# schematics.net
KiCad netlist of a schematic drawn in EAGLE
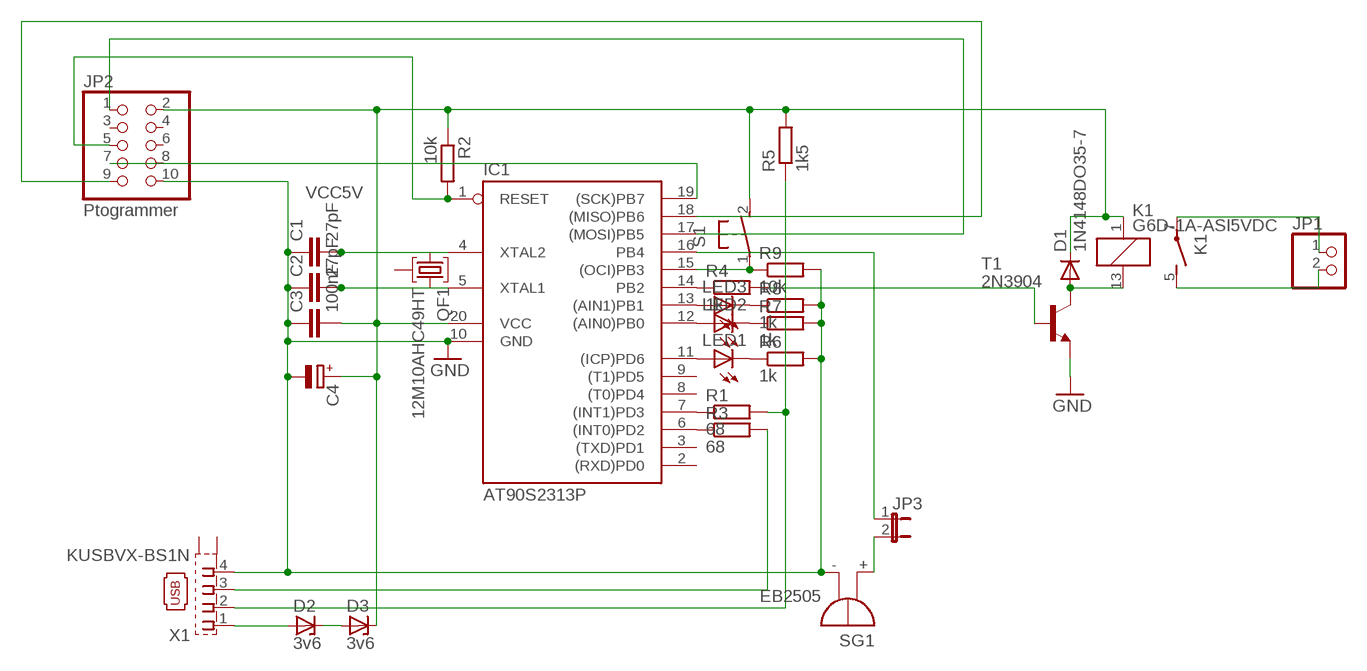
[diagram p0: schematic, sheet 1]

(export (version "E")
  (design (tool "Eeschema 10.0.6"))
  (components
    (comp (ref "C1")
      (value "27pF")
      (footprint "eagle-import:C025-024X044")
      (libsource (lib "eagle-import") (part "C-EU025-024X044"))
    )
    (comp (ref "C2")
      (value "27pF")
      (footprint "eagle-import:C025-024X044")
      (libsource (lib "eagle-import") (part "C-EU025-024X044"))
    )
    (comp (ref "C3")
      (value "100nF")
      (footprint "eagle-import:C025-024X044")
      (libsource (lib "eagle-import") (part "C-EU025-024X044"))
    )
    (comp (ref "C4")
      (value "CPOL-EUE2.5-7")
      (footprint "eagle-import:E2,5-7")
      (libsource (lib "eagle-import") (part "CPOL-EUE2.5-7"))
    )
    (comp (ref "D1")
      (value "1N4148DO35-7")
      (footprint "eagle-import:DO35-7")
      (libsource (lib "eagle-import") (part "1N4148DO35-7"))
    )
    (comp (ref "D2")
      (value "3v6")
      (footprint "eagle-import:DO35Z10")
      (libsource (lib "eagle-import") (part "ZENER-DIODEDO35Z10"))
    )
    (comp (ref "D3")
      (value "3v6")
      (footprint "eagle-import:DO35Z10")
      (libsource (lib "eagle-import") (part "ZENER-DIODEDO35Z10"))
    )
    (comp (ref "IC1")
      (value "AT90S2313P")
      (footprint "eagle-import:DIL20")
      (libsource (lib "eagle-import") (part "AT90S2313P"))
    )
    (comp (ref "JP1")
      (value "PINHD-1X2/90")
      (footprint "eagle-import:1X02_90")
      (libsource (lib "eagle-import") (part "PINHD-1X2/90"))
    )
    (comp (ref "JP2")
      (value "Ptogrammer")
      (footprint "eagle-import:2X05")
      (libsource (lib "eagle-import") (part "PINHD-2X5"))
    )
    (comp (ref "JP3")
      (value "JP1E")
      (footprint "eagle-import:JP1")
      (libsource (lib "eagle-import") (part "JP1E"))
    )
    (comp (ref "K1")
      (value "G6D-1A-ASI5VDC")
      (footprint "eagle-import:G6D")
      (libsource (lib "eagle-import") (part "G6D?-1A-ASI5VDC"))
    )
    (comp (ref "LED1")
      (value "LED3MM")
      (footprint "eagle-import:LED3MM")
      (libsource (lib "eagle-import") (part "LED3MM"))
    )
    (comp (ref "LED2")
      (value "LED3MM")
      (footprint "eagle-import:LED3MM")
      (libsource (lib "eagle-import") (part "LED3MM"))
    )
    (comp (ref "LED3")
      (value "LED3MM")
      (footprint "eagle-import:LED3MM")
      (libsource (lib "eagle-import") (part "LED3MM"))
    )
    (comp (ref "QF1")
      (value "12M10AHC49HT")
      (footprint "eagle-import:HC49U")
      (libsource (lib "eagle-import") (part "12M10AHC49HT"))
    )
    (comp (ref "R1")
      (value "68")
      (footprint "eagle-import:0204_5")
      (libsource (lib "eagle-import") (part "R-EU_0204/5"))
    )
    (comp (ref "R2")
      (value "10k")
      (footprint "eagle-import:0207_10")
      (libsource (lib "eagle-import") (part "R-EU_0207/10"))
    )
    (comp (ref "R3")
      (value "68")
      (footprint "eagle-import:0204_5")
      (libsource (lib "eagle-import") (part "R-EU_0204/5"))
    )
    (comp (ref "R4")
      (value "1k")
      (footprint "eagle-import:0204_5")
      (libsource (lib "eagle-import") (part "R-EU_0204/5"))
    )
    (comp (ref "R5")
      (value "1k5")
      (footprint "eagle-import:0204_5")
      (libsource (lib "eagle-import") (part "R-EU_0204/5"))
    )
    (comp (ref "R6")
      (value "1k")
      (footprint "eagle-import:0204_5")
      (libsource (lib "eagle-import") (part "R-EU_0204/5"))
    )
    (comp (ref "R7")
      (value "1k")
      (footprint "eagle-import:0204_5")
      (libsource (lib "eagle-import") (part "R-EU_0204/5"))
    )
    (comp (ref "R8")
      (value "1k")
      (footprint "eagle-import:0204_5")
      (libsource (lib "eagle-import") (part "R-EU_0204/5"))
    )
    (comp (ref "R9")
      (value "10k")
      (footprint "eagle-import:0207_10")
      (libsource (lib "eagle-import") (part "R-EU_0207/10"))
    )
    (comp (ref "S1")
      (value "31-XX")
      (footprint "eagle-import:B3F-31XX")
      (fields (field (name "MPN") "B3F-3100"))
      (libsource (lib "eagle-import") (part "31-XX"))
    )
    (comp (ref "SG1")
      (value "EB2505")
      (footprint "eagle-import:EB2505")
      (libsource (lib "eagle-import") (part "EB2505"))
    )
    (comp (ref "T1")
      (value "2N3904")
      (footprint "eagle-import:TO92-EBC")
      (libsource (lib "eagle-import") (part "-NPN-TO92-EBC2N2222"))
    )
    (comp (ref "X1")
      (value "KUSBVX-BS1N")
      (footprint "eagle-import:KUSBVX-BS1N")
      (libsource (lib "eagle-import") (part "KUSBVX-BS1N"))
    )
  )
  (nets
    (net (code "1") (name "/VCC5V") (class "Default")
      (node (ref "C3") (pin "2") (pinfunction "2_2") (pintype "passive"))
      (node (ref "C4") (pin "+") (pinfunction "+_+") (pintype "passive"))
      (node (ref "D1") (pin "C") (pinfunction "C_C") (pintype "passive"))
      (node (ref "D3") (pin "C") (pinfunction "C_C") (pintype "passive"))
      (node (ref "IC1") (pin "20") (pinfunction "VCC_20") (pintype "power_in"))
      (node (ref "JP2") (pin "2") (pinfunction "2_2") (pintype "passive"))
      (node (ref "K1") (pin "1") (pinfunction "1_1") (pintype "passive"))
      (node (ref "R2") (pin "1") (pinfunction "1_1") (pintype "passive"))
      (node (ref "R5") (pin "2") (pinfunction "2_2") (pintype "passive"))
      (node (ref "S1") (pin "2") (pinfunction "S_2") (pintype "passive"))
    )
    (net (code "2") (name "GND") (class "Default")
      (node (ref "C1") (pin "1") (pinfunction "1_1") (pintype "passive"))
      (node (ref "C2") (pin "1") (pinfunction "1_1") (pintype "passive"))
      (node (ref "C3") (pin "1") (pinfunction "1_1") (pintype "passive"))
      (node (ref "C4") (pin "-") (pinfunction "-_-") (pintype "passive"))
      (node (ref "IC1") (pin "10") (pinfunction "GND_10") (pintype "power_in"))
      (node (ref "JP2") (pin "10") (pinfunction "10_10") (pintype "passive"))
      (node (ref "R6") (pin "2") (pinfunction "2_2") (pintype "passive"))
      (node (ref "R7") (pin "2") (pinfunction "2_2") (pintype "passive"))
      (node (ref "R8") (pin "2") (pinfunction "2_2") (pintype "passive"))
      (node (ref "R9") (pin "2") (pinfunction "2_2") (pintype "passive"))
      (node (ref "SG1") (pin "-") (pinfunction "-_-") (pintype "passive"))
      (node (ref "T1") (pin "E") (pinfunction "E_E") (pintype "passive"))
      (node (ref "X1") (pin "4") (pinfunction "4_4") (pintype "passive"))
    )
    (net (code "3") (name "Net-(D2-PadA)") (class "Default")
      (node (ref "D2") (pin "A") (pinfunction "A_A") (pintype "passive"))
      (node (ref "X1") (pin "1") (pinfunction "1_1") (pintype "passive"))
    )
    (net (code "4") (name "Net-(D2-PadC)") (class "Default")
      (node (ref "D2") (pin "C") (pinfunction "C_C") (pintype "passive"))
      (node (ref "D3") (pin "A") (pinfunction "A_A") (pintype "passive"))
    )
    (net (code "5") (name "Net-(IC1-(AIN0)PB0)") (class "Default")
      (node (ref "IC1") (pin "12") (pinfunction "(AIN0)PB0_12") (pintype "bidirectional"))
      (node (ref "LED2") (pin "A") (pinfunction "A_A") (pintype "passive"))
    )
    (net (code "6") (name "Net-(IC1-(AIN1)PB1)") (class "Default")
      (node (ref "IC1") (pin "13") (pinfunction "(AIN1)PB1_13") (pintype "bidirectional"))
      (node (ref "LED3") (pin "A") (pinfunction "A_A") (pintype "passive"))
    )
    (net (code "7") (name "Net-(IC1-(ICP)PD6)") (class "Default")
      (node (ref "IC1") (pin "11") (pinfunction "(ICP)PD6_11") (pintype "bidirectional"))
      (node (ref "LED1") (pin "A") (pinfunction "A_A") (pintype "passive"))
    )
    (net (code "8") (name "Net-(IC1-(INT0)PD2)") (class "Default")
      (node (ref "IC1") (pin "6") (pinfunction "(INT0)PD2_6") (pintype "bidirectional"))
      (node (ref "R3") (pin "1") (pinfunction "1_1") (pintype "passive"))
    )
    (net (code "9") (name "Net-(IC1-(INT1)PD3)") (class "Default")
      (node (ref "IC1") (pin "7") (pinfunction "(INT1)PD3_7") (pintype "bidirectional"))
      (node (ref "R1") (pin "1") (pinfunction "1_1") (pintype "passive"))
    )
    (net (code "10") (name "Net-(IC1-(MISO)PB6)") (class "Default")
      (node (ref "IC1") (pin "18") (pinfunction "(MISO)PB6_18") (pintype "bidirectional"))
      (node (ref "JP2") (pin "9") (pinfunction "9_9") (pintype "passive"))
    )
    (net (code "11") (name "Net-(IC1-(MOSI)PB5)") (class "Default")
      (node (ref "IC1") (pin "17") (pinfunction "(MOSI)PB5_17") (pintype "bidirectional"))
      (node (ref "JP2") (pin "1") (pinfunction "1_1") (pintype "passive"))
    )
    (net (code "12") (name "Net-(IC1-(OCI)PB3)") (class "Default")
      (node (ref "IC1") (pin "15") (pinfunction "(OCI)PB3_15") (pintype "bidirectional"))
      (node (ref "R9") (pin "1") (pinfunction "1_1") (pintype "passive"))
      (node (ref "S1") (pin "1") (pinfunction "P_1") (pintype "passive"))
    )
    (net (code "13") (name "Net-(IC1-(SCK)PB7)") (class "Default")
      (node (ref "IC1") (pin "19") (pinfunction "(SCK)PB7_19") (pintype "bidirectional"))
      (node (ref "JP2") (pin "7") (pinfunction "7_7") (pintype "passive"))
    )
    (net (code "14") (name "Net-(IC1-PB2)") (class "Default")
      (node (ref "IC1") (pin "14") (pinfunction "PB2_14") (pintype "bidirectional"))
      (node (ref "R4") (pin "1") (pinfunction "1_1") (pintype "passive"))
    )
    (net (code "15") (name "Net-(IC1-PB4)") (class "Default")
      (node (ref "IC1") (pin "16") (pinfunction "PB4_16") (pintype "bidirectional"))
      (node (ref "JP3") (pin "1") (pinfunction "1_1") (pintype "passive"))
    )
    (net (code "16") (name "Net-(IC1-RESET)") (class "Default")
      (node (ref "IC1") (pin "1") (pinfunction "RESET_1") (pintype "bidirectional"))
      (node (ref "JP2") (pin "5") (pinfunction "5_5") (pintype "passive"))
      (node (ref "R2") (pin "2") (pinfunction "2_2") (pintype "passive"))
    )
    (net (code "17") (name "Net-(IC1-XTAL1)") (class "Default")
      (node (ref "C2") (pin "2") (pinfunction "2_2") (pintype "passive"))
      (node (ref "IC1") (pin "5") (pinfunction "XTAL1_5") (pintype "bidirectional"))
      (node (ref "QF1") (pin "3") (pinfunction "3_3") (pintype "passive"))
    )
    (net (code "18") (name "Net-(IC1-XTAL2)") (class "Default")
      (node (ref "C1") (pin "2") (pinfunction "2_2") (pintype "passive"))
      (node (ref "IC1") (pin "4") (pinfunction "XTAL2_4") (pintype "bidirectional"))
      (node (ref "QF1") (pin "1") (pinfunction "1_1") (pintype "passive"))
    )
    (net (code "19") (name "Net-(JP3-Pad2)") (class "Default")
      (node (ref "JP3") (pin "2") (pinfunction "2_2") (pintype "passive"))
      (node (ref "SG1") (pin "+") (pinfunction "+_+") (pintype "passive"))
    )
    (net (code "20") (name "Net-(K1A-2)") (class "Default")
      (node (ref "D1") (pin "A") (pinfunction "A_A") (pintype "passive"))
      (node (ref "K1") (pin "13") (pinfunction "2_13") (pintype "passive"))
      (node (ref "T1") (pin "C") (pinfunction "C_C") (pintype "passive"))
    )
    (net (code "21") (name "Net-(K1B-P)") (class "Default")
      (node (ref "JP1") (pin "1") (pinfunction "1_1") (pintype "passive"))
      (node (ref "K1") (pin "7") (pinfunction "P_7") (pintype "passive"))
    )
    (net (code "22") (name "Net-(K1B-S)") (class "Default")
      (node (ref "JP1") (pin "2") (pinfunction "2_2") (pintype "passive"))
      (node (ref "K1") (pin "5") (pinfunction "S_5") (pintype "passive"))
    )
    (net (code "23") (name "Net-(LED1-C)") (class "Default")
      (node (ref "LED1") (pin "K") (pinfunction "C_K") (pintype "passive"))
      (node (ref "R6") (pin "1") (pinfunction "1_1") (pintype "passive"))
    )
    (net (code "24") (name "Net-(LED2-C)") (class "Default")
      (node (ref "LED2") (pin "K") (pinfunction "C_K") (pintype "passive"))
      (node (ref "R7") (pin "1") (pinfunction "1_1") (pintype "passive"))
    )
    (net (code "25") (name "Net-(LED3-C)") (class "Default")
      (node (ref "LED3") (pin "K") (pinfunction "C_K") (pintype "passive"))
      (node (ref "R8") (pin "1") (pinfunction "1_1") (pintype "passive"))
    )
    (net (code "26") (name "Net-(R1-Pad2)") (class "Default")
      (node (ref "R1") (pin "2") (pinfunction "2_2") (pintype "passive"))
      (node (ref "R5") (pin "1") (pinfunction "1_1") (pintype "passive"))
      (node (ref "X1") (pin "2") (pinfunction "2_2") (pintype "passive"))
    )
    (net (code "27") (name "Net-(R3-Pad2)") (class "Default")
      (node (ref "R3") (pin "2") (pinfunction "2_2") (pintype "passive"))
      (node (ref "X1") (pin "3") (pinfunction "3_3") (pintype "passive"))
    )
    (net (code "28") (name "Net-(R4-Pad2)") (class "Default")
      (node (ref "R4") (pin "2") (pinfunction "2_2") (pintype "passive"))
      (node (ref "T1") (pin "B") (pinfunction "B_B") (pintype "passive"))
    )
    (net (code "29") (name "unconnected-(IC1-(RXD)PD0-Pad2)") (class "Default")
      (node (ref "IC1") (pin "2") (pinfunction "(RXD)PD0_2") (pintype "bidirectional"))
    )
    (net (code "30") (name "unconnected-(IC1-(T0)PD4-Pad8)") (class "Default")
      (node (ref "IC1") (pin "8") (pinfunction "(T0)PD4_8") (pintype "bidirectional"))
    )
    (net (code "31") (name "unconnected-(IC1-(T1)PD5-Pad9)") (class "Default")
      (node (ref "IC1") (pin "9") (pinfunction "(T1)PD5_9") (pintype "bidirectional"))
    )
    (net (code "32") (name "unconnected-(IC1-(TXD)PD1-Pad3)") (class "Default")
      (node (ref "IC1") (pin "3") (pinfunction "(TXD)PD1_3") (pintype "bidirectional"))
    )
    (net (code "33") (name "unconnected-(JP2-Pad3)") (class "Default")
      (node (ref "JP2") (pin "3") (pinfunction "3_3") (pintype "passive"))
    )
    (net (code "34") (name "unconnected-(JP2-Pad4)") (class "Default")
      (node (ref "JP2") (pin "4") (pinfunction "4_4") (pintype "passive"))
    )
    (net (code "35") (name "unconnected-(JP2-Pad6)") (class "Default")
      (node (ref "JP2") (pin "6") (pinfunction "6_6") (pintype "passive"))
    )
    (net (code "36") (name "unconnected-(JP2-Pad8)") (class "Default")
      (node (ref "JP2") (pin "8") (pinfunction "8_8") (pintype "passive"))
    )
    (net (code "37") (name "unconnected-(QF1-Pad2)") (class "Default")
      (node (ref "QF1") (pin "2") (pinfunction "2_2") (pintype "passive"))
    )
    (net (code "38") (name "unconnected-(X1-S1-PadM1)") (class "Default")
      (node (ref "X1") (pin "M1") (pinfunction "S1_M1") (pintype "passive"))
    )
    (net (code "39") (name "unconnected-(X1-S2-PadM2)") (class "Default")
      (node (ref "X1") (pin "M2") (pinfunction "S2_M2") (pintype "passive"))
    )
  )
)
